# USB_charger_circuit.net
KiCad netlist of a schematic drawn in EAGLE
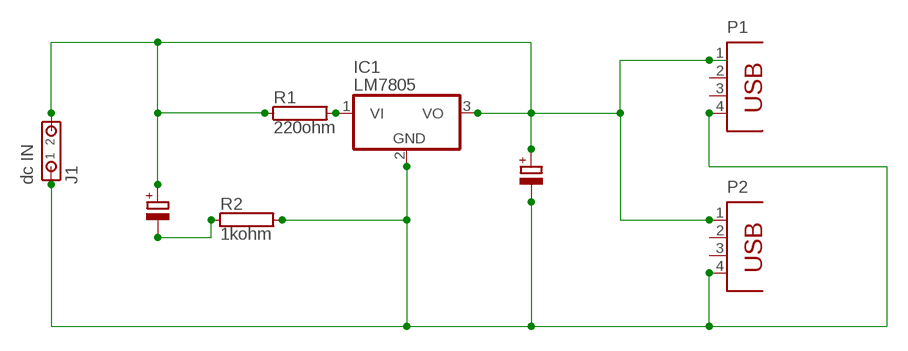
[diagram p0: schematic, sheet 1]

(export (version "E")
  (design (tool "Eeschema 10.0.6"))
  (components
    (comp (ref "IC1")
      (value "LM7805")
      (footprint "eagle-import:TO220H")
      (libsource (lib "eagle-import") (part "78T12"))
    )
    (comp (ref "J1")
      (value "dc IN")
      (footprint "eagle-import:794681-2")
      (libsource (lib "eagle-import") (part "794681-2"))
    )
    (comp (ref "P1")
      (value "PN87520")
      (footprint "eagle-import:PN87520")
      (libsource (lib "eagle-import") (part "PN87520"))
    )
    (comp (ref "P2")
      (value "PN87520")
      (footprint "eagle-import:PN87520")
      (libsource (lib "eagle-import") (part "PN87520"))
    )
    (comp (ref "R1")
      (value "220ohm")
      (footprint "eagle-import:AC01")
      (libsource (lib "eagle-import") (part "RAC01"))
    )
    (comp (ref "R2")
      (value "1kohm")
      (footprint "eagle-import:AC01")
      (libsource (lib "eagle-import") (part "RAC01"))
    )
  )
  (nets
    (net (code "1") (name "Net-(IC1-GND)") (class "Default")
      (node (ref "IC1") (pin "2") (pinfunction "GND_2") (pintype "passive"))
      (node (ref "J1") (pin "1") (pinfunction "1_1") (pintype "passive"))
      (node (ref "P1") (pin "4") (pinfunction "4_4") (pintype "passive"))
      (node (ref "P2") (pin "4") (pinfunction "4_4") (pintype "passive"))
      (node (ref "R2") (pin "2") (pinfunction "2_2") (pintype "passive"))
    )
    (net (code "2") (name "Net-(IC1-VI)") (class "Default")
      (node (ref "IC1") (pin "1") (pinfunction "VI_1") (pintype "input"))
      (node (ref "R1") (pin "2") (pinfunction "2_2") (pintype "passive"))
    )
    (net (code "3") (name "Net-(IC1-VO)") (class "Default")
      (node (ref "IC1") (pin "3") (pinfunction "VO_3") (pintype "passive"))
      (node (ref "J1") (pin "2") (pinfunction "2_2") (pintype "passive"))
      (node (ref "P1") (pin "1") (pinfunction "1_1") (pintype "passive"))
      (node (ref "P2") (pin "1") (pinfunction "1_1") (pintype "passive"))
      (node (ref "R1") (pin "1") (pinfunction "1_1") (pintype "passive"))
    )
    (net (code "4") (name "unconnected-(P1-Pad2)") (class "Default")
      (node (ref "P1") (pin "2") (pinfunction "2_2") (pintype "passive"))
    )
    (net (code "5") (name "unconnected-(P1-Pad3)") (class "Default")
      (node (ref "P1") (pin "3") (pinfunction "3_3") (pintype "passive"))
    )
    (net (code "6") (name "unconnected-(P2-Pad2)") (class "Default")
      (node (ref "P2") (pin "2") (pinfunction "2_2") (pintype "passive"))
    )
    (net (code "7") (name "unconnected-(P2-Pad3)") (class "Default")
      (node (ref "P2") (pin "3") (pinfunction "3_3") (pintype "passive"))
    )
    (net (code "8") (name "unconnected-(R2-Pad1)") (class "Default")
      (node (ref "R2") (pin "1") (pinfunction "1_1") (pintype "passive"))
    )
  )
)
